# flower.net
KiCad netlist of a schematic drawn in EAGLE
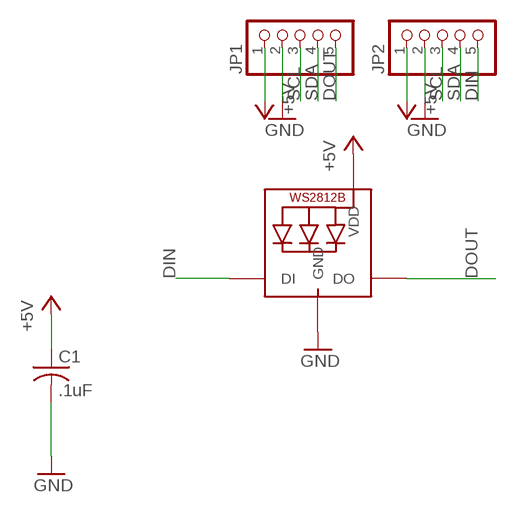
[diagram p0: schematic, sheet 1]

(export (version "E")
  (design (tool "Eeschema 10.0.6"))
  (components
    (comp (ref "C1")
      (value ".1uF")
      (footprint "eagle-import:C0805")
      (libsource (lib "eagle-import") (part "C-USC0805"))
    )
    (comp (ref "JP1")
      (value "PINHD-1X55X2MM")
      (footprint "eagle-import:1_05X2MM")
      (libsource (lib "eagle-import") (part "PINHD-1X55X2MM"))
    )
    (comp (ref "JP2")
      (value "PINHD-1X55X2MM")
      (footprint "eagle-import:1_05X2MM")
      (libsource (lib "eagle-import") (part "PINHD-1X55X2MM"))
    )
    (comp (ref "LED1")
      (value "WS2812B_5050N")
      (footprint "eagle-import:WS2812B-NARROW")
      (libsource (lib "eagle-import") (part "WS2812B_5050N"))
    )
  )
  (nets
    (net (code "1") (name "+5V") (class "Default")
      (node (ref "C1") (pin "1") (pinfunction "1_1") (pintype "passive"))
      (node (ref "JP1") (pin "1") (pinfunction "1_1") (pintype "passive"))
      (node (ref "JP2") (pin "1") (pinfunction "1_1") (pintype "passive"))
      (node (ref "LED1") (pin "1-VDD") (pinfunction "VDD_1-VDD") (pintype "power_in"))
    )
    (net (code "2") (name "/DIN") (class "Default")
      (node (ref "JP2") (pin "5") (pinfunction "5_5") (pintype "passive"))
      (node (ref "LED1") (pin "4-DIN") (pinfunction "DI_4-DIN") (pintype "input"))
    )
    (net (code "3") (name "/DOUT") (class "Default")
      (node (ref "JP1") (pin "5") (pinfunction "5_5") (pintype "passive"))
      (node (ref "LED1") (pin "2-DOUT") (pinfunction "DO_2-DOUT") (pintype "output"))
    )
    (net (code "4") (name "/SCL") (class "Default")
      (node (ref "JP1") (pin "3") (pinfunction "3_3") (pintype "passive"))
      (node (ref "JP2") (pin "3") (pinfunction "3_3") (pintype "passive"))
    )
    (net (code "5") (name "/SDA") (class "Default")
      (node (ref "JP1") (pin "4") (pinfunction "4_4") (pintype "passive"))
      (node (ref "JP2") (pin "4") (pinfunction "4_4") (pintype "passive"))
    )
    (net (code "6") (name "GND") (class "Default")
      (node (ref "C1") (pin "2") (pinfunction "2_2") (pintype "passive"))
      (node (ref "JP1") (pin "2") (pinfunction "2_2") (pintype "passive"))
      (node (ref "JP2") (pin "2") (pinfunction "2_2") (pintype "passive"))
      (node (ref "LED1") (pin "3-GND") (pinfunction "GND_3-GND") (pintype "power_in"))
    )
  )
)
